# VGA.net
KiCad netlist of a schematic drawn in Altium Designer
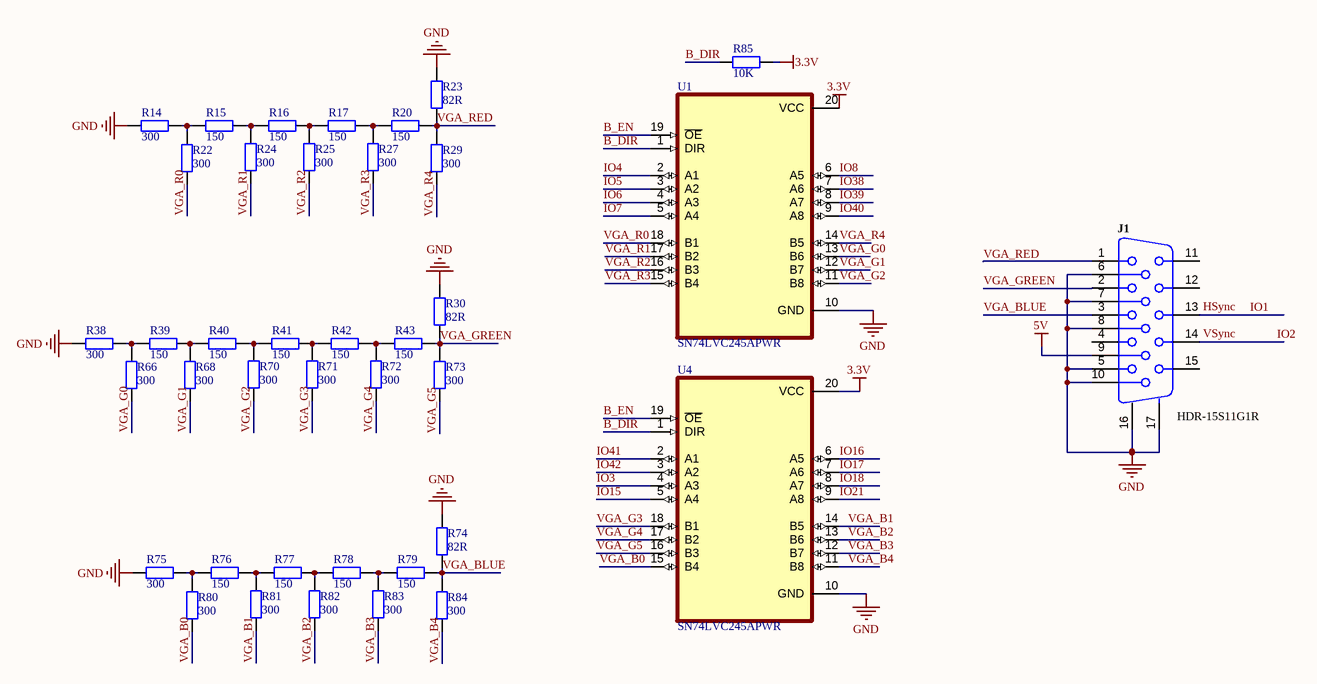
[diagram p0: VGA.SchDoc]

(export (version "E")
  (design (tool "Eeschema 10.0.6"))
  (components
    (comp (ref "J1")
      (value "HDR-15S11G1R")
      (footprint "DB15-VGA-Female")
      (description "Socket, High-Density DB15 (HD15) R/A Female Through-hole")
      (libsource (lib "My Library") (part "CON 15 Female"))
    )
    (comp (ref "R14")
      (value "300")
      (footprint "RES-0603")
      (description "Resistor")
      (fields (field (name "Comment") "Res2") (field (name "PUBLISHER") "Altium Limited"))
      (libsource (lib "") (part "Res2_1"))
    )
    (comp (ref "R15")
      (value "150")
      (footprint "RES-0603")
      (description "Resistor")
      (fields (field (name "Comment") "Res2") (field (name "PUBLISHER") "Altium Limited"))
      (libsource (lib "") (part "Res2_1"))
    )
    (comp (ref "R16")
      (value "150")
      (footprint "RES-0603")
      (description "Resistor")
      (fields (field (name "Comment") "Res2") (field (name "PUBLISHER") "Altium Limited"))
      (libsource (lib "") (part "Res2_1"))
    )
    (comp (ref "R17")
      (value "150")
      (footprint "RES-0603")
      (description "Resistor")
      (fields (field (name "Comment") "Res2") (field (name "PUBLISHER") "Altium Limited"))
      (libsource (lib "") (part "Res2_1"))
    )
    (comp (ref "R20")
      (value "150")
      (footprint "RES-0603")
      (description "Resistor")
      (fields (field (name "Comment") "Res2") (field (name "PUBLISHER") "Altium Limited"))
      (libsource (lib "") (part "Res2_1"))
    )
    (comp (ref "R22")
      (value "300")
      (footprint "RES-0603")
      (description "Resistor")
      (fields (field (name "Comment") "Res2") (field (name "PUBLISHER") "Altium Limited"))
      (libsource (lib "Miscellaneous Devices") (part "Res2"))
    )
    (comp (ref "R23")
      (value "82R")
      (footprint "RES-0603")
      (description "Resistor")
      (fields (field (name "Comment") "Res2") (field (name "PUBLISHER") "Altium Limited"))
      (libsource (lib "") (part "Res2_2"))
    )
    (comp (ref "R24")
      (value "300")
      (footprint "RES-0603")
      (description "Resistor")
      (fields (field (name "Comment") "Res2") (field (name "PUBLISHER") "Altium Limited"))
      (libsource (lib "Miscellaneous Devices") (part "Res2"))
    )
    (comp (ref "R25")
      (value "300")
      (footprint "RES-0603")
      (description "Resistor")
      (fields (field (name "Comment") "Res2") (field (name "PUBLISHER") "Altium Limited"))
      (libsource (lib "Miscellaneous Devices") (part "Res2"))
    )
    (comp (ref "R27")
      (value "300")
      (footprint "RES-0603")
      (description "Resistor")
      (fields (field (name "Comment") "Res2") (field (name "PUBLISHER") "Altium Limited"))
      (libsource (lib "Miscellaneous Devices") (part "Res2"))
    )
    (comp (ref "R29")
      (value "300")
      (footprint "RES-0603")
      (description "Resistor")
      (fields (field (name "Comment") "Res2") (field (name "PUBLISHER") "Altium Limited"))
      (libsource (lib "Miscellaneous Devices") (part "Res2"))
    )
    (comp (ref "R30")
      (value "82R")
      (footprint "RES-0603")
      (description "Resistor")
      (fields (field (name "Comment") "Res2") (field (name "PUBLISHER") "Altium Limited"))
      (libsource (lib "") (part "Res2_2"))
    )
    (comp (ref "R38")
      (value "300")
      (footprint "RES-0603")
      (description "Resistor")
      (fields (field (name "Comment") "Res2") (field (name "PUBLISHER") "Altium Limited"))
      (libsource (lib "") (part "Res2_1"))
    )
    (comp (ref "R39")
      (value "150")
      (footprint "RES-0603")
      (description "Resistor")
      (fields (field (name "Comment") "Res2") (field (name "PUBLISHER") "Altium Limited"))
      (libsource (lib "") (part "Res2_1"))
    )
    (comp (ref "R40")
      (value "150")
      (footprint "RES-0603")
      (description "Resistor")
      (fields (field (name "Comment") "Res2") (field (name "PUBLISHER") "Altium Limited"))
      (libsource (lib "") (part "Res2_1"))
    )
    (comp (ref "R41")
      (value "150")
      (footprint "RES-0603")
      (description "Resistor")
      (fields (field (name "Comment") "Res2") (field (name "PUBLISHER") "Altium Limited"))
      (libsource (lib "") (part "Res2_1"))
    )
    (comp (ref "R42")
      (value "150")
      (footprint "RES-0603")
      (description "Resistor")
      (fields (field (name "Comment") "Res2") (field (name "PUBLISHER") "Altium Limited"))
      (libsource (lib "") (part "Res2_1"))
    )
    (comp (ref "R43")
      (value "150")
      (footprint "RES-0603")
      (description "Resistor")
      (fields (field (name "Comment") "Res2") (field (name "PUBLISHER") "Altium Limited"))
      (libsource (lib "") (part "Res2_1"))
    )
    (comp (ref "R66")
      (value "300")
      (footprint "RES-0603")
      (description "Resistor")
      (fields (field (name "Comment") "Res2") (field (name "PUBLISHER") "Altium Limited"))
      (libsource (lib "Miscellaneous Devices") (part "Res2"))
    )
    (comp (ref "R68")
      (value "300")
      (footprint "RES-0603")
      (description "Resistor")
      (fields (field (name "Comment") "Res2") (field (name "PUBLISHER") "Altium Limited"))
      (libsource (lib "Miscellaneous Devices") (part "Res2"))
    )
    (comp (ref "R70")
      (value "300")
      (footprint "RES-0603")
      (description "Resistor")
      (fields (field (name "Comment") "Res2") (field (name "PUBLISHER") "Altium Limited"))
      (libsource (lib "Miscellaneous Devices") (part "Res2"))
    )
    (comp (ref "R71")
      (value "300")
      (footprint "RES-0603")
      (description "Resistor")
      (fields (field (name "Comment") "Res2") (field (name "PUBLISHER") "Altium Limited"))
      (libsource (lib "Miscellaneous Devices") (part "Res2"))
    )
    (comp (ref "R72")
      (value "300")
      (footprint "RES-0603")
      (description "Resistor")
      (fields (field (name "Comment") "Res2") (field (name "PUBLISHER") "Altium Limited"))
      (libsource (lib "Miscellaneous Devices") (part "Res2"))
    )
    (comp (ref "R73")
      (value "300")
      (footprint "RES-0603")
      (description "Resistor")
      (fields (field (name "Comment") "Res2") (field (name "PUBLISHER") "Altium Limited"))
      (libsource (lib "Miscellaneous Devices") (part "Res2"))
    )
    (comp (ref "R74")
      (value "82R")
      (footprint "RES-0603")
      (description "Resistor")
      (fields (field (name "Comment") "Res2") (field (name "PUBLISHER") "Altium Limited"))
      (libsource (lib "") (part "Res2_2"))
    )
    (comp (ref "R75")
      (value "300")
      (footprint "RES-0603")
      (description "Resistor")
      (fields (field (name "Comment") "Res2") (field (name "PUBLISHER") "Altium Limited"))
      (libsource (lib "") (part "Res2_1"))
    )
    (comp (ref "R76")
      (value "150")
      (footprint "RES-0603")
      (description "Resistor")
      (fields (field (name "Comment") "Res2") (field (name "PUBLISHER") "Altium Limited"))
      (libsource (lib "") (part "Res2_1"))
    )
    (comp (ref "R77")
      (value "150")
      (footprint "RES-0603")
      (description "Resistor")
      (fields (field (name "Comment") "Res2") (field (name "PUBLISHER") "Altium Limited"))
      (libsource (lib "") (part "Res2_1"))
    )
    (comp (ref "R78")
      (value "150")
      (footprint "RES-0603")
      (description "Resistor")
      (fields (field (name "Comment") "Res2") (field (name "PUBLISHER") "Altium Limited"))
      (libsource (lib "") (part "Res2_1"))
    )
    (comp (ref "R79")
      (value "150")
      (footprint "RES-0603")
      (description "Resistor")
      (fields (field (name "Comment") "Res2") (field (name "PUBLISHER") "Altium Limited"))
      (libsource (lib "") (part "Res2_1"))
    )
    (comp (ref "R80")
      (value "300")
      (footprint "RES-0603")
      (description "Resistor")
      (fields (field (name "Comment") "Res2") (field (name "PUBLISHER") "Altium Limited"))
      (libsource (lib "Miscellaneous Devices") (part "Res2"))
    )
    (comp (ref "R81")
      (value "300")
      (footprint "RES-0603")
      (description "Resistor")
      (fields (field (name "Comment") "Res2") (field (name "PUBLISHER") "Altium Limited"))
      (libsource (lib "Miscellaneous Devices") (part "Res2"))
    )
    (comp (ref "R82")
      (value "300")
      (footprint "RES-0603")
      (description "Resistor")
      (fields (field (name "Comment") "Res2") (field (name "PUBLISHER") "Altium Limited"))
      (libsource (lib "Miscellaneous Devices") (part "Res2"))
    )
    (comp (ref "R83")
      (value "300")
      (footprint "RES-0603")
      (description "Resistor")
      (fields (field (name "Comment") "Res2") (field (name "PUBLISHER") "Altium Limited"))
      (libsource (lib "Miscellaneous Devices") (part "Res2"))
    )
    (comp (ref "R84")
      (value "300")
      (footprint "RES-0603")
      (description "Resistor")
      (fields (field (name "Comment") "Res2") (field (name "PUBLISHER") "Altium Limited"))
      (libsource (lib "Miscellaneous Devices") (part "Res2"))
    )
    (comp (ref "R85")
      (value "10K")
      (footprint "RES-0603")
      (description "Resistor")
      (fields (field (name "Comment") "Res2") (field (name "PUBLISHER") "Altium Limited"))
      (libsource (lib "") (part "Res2_1"))
    )
    (comp (ref "U1")
      (value "SN74LVC245APWR")
      (footprint "SOP65P640X120-20N")
      (description "Octal Bus Transceiver With 3-State Outputs 20-TSSOP -40 to 125")
      (fields (field (name "MF") "Texas Instruments"))
      (libsource (lib "SN74LVC245APWR") (part "SN74LVC245APWR"))
    )
    (comp (ref "U4")
      (value "SN74LVC245APWR")
      (footprint "SOP65P640X120-20N")
      (description "Octal Bus Transceiver With 3-State Outputs 20-TSSOP -40 to 125")
      (fields (field (name "MF") "Texas Instruments"))
      (libsource (lib "SN74LVC245APWR") (part "SN74LVC245APWR"))
    )
  )
  (nets
    (net (code "1") (name "/B_DIR") (class "Default")
      (node (ref "R85") (pin "2") (pinfunction "2_2") (pintype "passive"))
      (node (ref "U1") (pin "1") (pinfunction "DIR_1") (pintype "input"))
      (node (ref "U4") (pin "1") (pinfunction "DIR_1") (pintype "input"))
    )
    (net (code "2") (name "/B_EN") (class "Default")
      (node (ref "U1") (pin "19") (pinfunction "~{OE}_19") (pintype "input"))
      (node (ref "U4") (pin "19") (pinfunction "~{OE}_19") (pintype "input"))
    )
    (net (code "4") (name "/IO1") (class "Default")
      (node (ref "J1") (pin "13") (pinfunction "13_13") (pintype "passive"))
    )
    (net (code "5") (name "/IO2") (class "Default")
      (node (ref "J1") (pin "14") (pinfunction "14_14") (pintype "passive"))
    )
    (net (code "6") (name "/IO3") (class "Default")
      (node (ref "U4") (pin "4") (pinfunction "A3_4") (pintype "bidirectional"))
    )
    (net (code "7") (name "/IO4") (class "Default")
      (node (ref "U1") (pin "2") (pinfunction "A1_2") (pintype "bidirectional"))
    )
    (net (code "8") (name "/IO5") (class "Default")
      (node (ref "U1") (pin "3") (pinfunction "A2_3") (pintype "bidirectional"))
    )
    (net (code "9") (name "/IO6") (class "Default")
      (node (ref "U1") (pin "4") (pinfunction "A3_4") (pintype "bidirectional"))
    )
    (net (code "10") (name "/IO7") (class "Default")
      (node (ref "U1") (pin "5") (pinfunction "A4_5") (pintype "bidirectional"))
    )
    (net (code "11") (name "/IO8") (class "Default")
      (node (ref "U1") (pin "6") (pinfunction "A5_6") (pintype "bidirectional"))
    )
    (net (code "12") (name "/IO15") (class "Default")
      (node (ref "U4") (pin "5") (pinfunction "A4_5") (pintype "bidirectional"))
    )
    (net (code "13") (name "/IO16") (class "Default")
      (node (ref "U4") (pin "6") (pinfunction "A5_6") (pintype "bidirectional"))
    )
    (net (code "14") (name "/IO17") (class "Default")
      (node (ref "U4") (pin "7") (pinfunction "A6_7") (pintype "bidirectional"))
    )
    (net (code "15") (name "/IO18") (class "Default")
      (node (ref "U4") (pin "8") (pinfunction "A7_8") (pintype "bidirectional"))
    )
    (net (code "16") (name "/IO21") (class "Default")
      (node (ref "U4") (pin "9") (pinfunction "A8_9") (pintype "bidirectional"))
    )
    (net (code "17") (name "/IO38") (class "Default")
      (node (ref "U1") (pin "7") (pinfunction "A6_7") (pintype "bidirectional"))
    )
    (net (code "18") (name "/IO39") (class "Default")
      (node (ref "U1") (pin "8") (pinfunction "A7_8") (pintype "bidirectional"))
    )
    (net (code "19") (name "/IO40") (class "Default")
      (node (ref "U1") (pin "9") (pinfunction "A8_9") (pintype "bidirectional"))
    )
    (net (code "20") (name "/IO41") (class "Default")
      (node (ref "U4") (pin "2") (pinfunction "A1_2") (pintype "bidirectional"))
    )
    (net (code "21") (name "/IO42") (class "Default")
      (node (ref "U4") (pin "3") (pinfunction "A2_3") (pintype "bidirectional"))
    )
    (net (code "22") (name "/VGA_B0") (class "Default")
      (node (ref "R80") (pin "2") (pinfunction "2_2") (pintype "passive"))
      (node (ref "U4") (pin "15") (pinfunction "B4_15") (pintype "bidirectional"))
    )
    (net (code "23") (name "/VGA_B1") (class "Default")
      (node (ref "R81") (pin "2") (pinfunction "2_2") (pintype "passive"))
      (node (ref "U4") (pin "14") (pinfunction "B5_14") (pintype "bidirectional"))
    )
    (net (code "24") (name "/VGA_B2") (class "Default")
      (node (ref "R82") (pin "2") (pinfunction "2_2") (pintype "passive"))
      (node (ref "U4") (pin "13") (pinfunction "B6_13") (pintype "bidirectional"))
    )
    (net (code "25") (name "/VGA_B3") (class "Default")
      (node (ref "R83") (pin "2") (pinfunction "2_2") (pintype "passive"))
      (node (ref "U4") (pin "12") (pinfunction "B7_12") (pintype "bidirectional"))
    )
    (net (code "26") (name "/VGA_B4") (class "Default")
      (node (ref "R84") (pin "2") (pinfunction "2_2") (pintype "passive"))
      (node (ref "U4") (pin "11") (pinfunction "B8_11") (pintype "bidirectional"))
    )
    (net (code "27") (name "/VGA_BLUE") (class "Default")
      (node (ref "J1") (pin "3") (pinfunction "3_3") (pintype "passive"))
      (node (ref "R74") (pin "1") (pinfunction "1_1") (pintype "passive"))
      (node (ref "R79") (pin "1") (pinfunction "1_1") (pintype "passive"))
      (node (ref "R84") (pin "1") (pinfunction "1_1") (pintype "passive"))
    )
    (net (code "28") (name "/VGA_G0") (class "Default")
      (node (ref "R66") (pin "2") (pinfunction "2_2") (pintype "passive"))
      (node (ref "U1") (pin "13") (pinfunction "B6_13") (pintype "bidirectional"))
    )
    (net (code "29") (name "/VGA_G1") (class "Default")
      (node (ref "R68") (pin "2") (pinfunction "2_2") (pintype "passive"))
      (node (ref "U1") (pin "12") (pinfunction "B7_12") (pintype "bidirectional"))
    )
    (net (code "30") (name "/VGA_G2") (class "Default")
      (node (ref "R70") (pin "2") (pinfunction "2_2") (pintype "passive"))
      (node (ref "U1") (pin "11") (pinfunction "B8_11") (pintype "bidirectional"))
    )
    (net (code "31") (name "/VGA_G3") (class "Default")
      (node (ref "R71") (pin "2") (pinfunction "2_2") (pintype "passive"))
      (node (ref "U4") (pin "18") (pinfunction "B1_18") (pintype "bidirectional"))
    )
    (net (code "32") (name "/VGA_G4") (class "Default")
      (node (ref "R72") (pin "2") (pinfunction "2_2") (pintype "passive"))
      (node (ref "U4") (pin "17") (pinfunction "B2_17") (pintype "bidirectional"))
    )
    (net (code "33") (name "/VGA_G5") (class "Default")
      (node (ref "R73") (pin "2") (pinfunction "2_2") (pintype "passive"))
      (node (ref "U4") (pin "16") (pinfunction "B3_16") (pintype "bidirectional"))
    )
    (net (code "34") (name "/VGA_GREEN") (class "Default")
      (node (ref "J1") (pin "2") (pinfunction "2_2") (pintype "passive"))
      (node (ref "R30") (pin "1") (pinfunction "1_1") (pintype "passive"))
      (node (ref "R43") (pin "1") (pinfunction "1_1") (pintype "passive"))
      (node (ref "R73") (pin "1") (pinfunction "1_1") (pintype "passive"))
    )
    (net (code "35") (name "/VGA_R0") (class "Default")
      (node (ref "R22") (pin "2") (pinfunction "2_2") (pintype "passive"))
      (node (ref "U1") (pin "18") (pinfunction "B1_18") (pintype "bidirectional"))
    )
    (net (code "36") (name "/VGA_R1") (class "Default")
      (node (ref "R24") (pin "2") (pinfunction "2_2") (pintype "passive"))
      (node (ref "U1") (pin "17") (pinfunction "B2_17") (pintype "bidirectional"))
    )
    (net (code "37") (name "/VGA_R2") (class "Default")
      (node (ref "R25") (pin "2") (pinfunction "2_2") (pintype "passive"))
      (node (ref "U1") (pin "16") (pinfunction "B3_16") (pintype "bidirectional"))
    )
    (net (code "38") (name "/VGA_R3") (class "Default")
      (node (ref "R27") (pin "2") (pinfunction "2_2") (pintype "passive"))
      (node (ref "U1") (pin "15") (pinfunction "B4_15") (pintype "bidirectional"))
    )
    (net (code "39") (name "/VGA_R4") (class "Default")
      (node (ref "R29") (pin "2") (pinfunction "2_2") (pintype "passive"))
      (node (ref "U1") (pin "14") (pinfunction "B5_14") (pintype "bidirectional"))
    )
    (net (code "40") (name "/VGA_RED") (class "Default")
      (node (ref "J1") (pin "1") (pinfunction "1_1") (pintype "passive"))
      (node (ref "R20") (pin "1") (pinfunction "1_1") (pintype "passive"))
      (node (ref "R23") (pin "1") (pinfunction "1_1") (pintype "passive"))
      (node (ref "R29") (pin "1") (pinfunction "1_1") (pintype "passive"))
    )
    (net (code "42") (name "3.3V") (class "Default")
      (node (ref "R85") (pin "1") (pinfunction "1_1") (pintype "passive"))
      (node (ref "U1") (pin "20") (pinfunction "VCC_20") (pintype "power_in"))
      (node (ref "U4") (pin "20") (pinfunction "VCC_20") (pintype "power_in"))
    )
    (net (code "43") (name "5V") (class "Default")
      (node (ref "J1") (pin "9") (pinfunction "9_9") (pintype "passive"))
    )
    (net (code "44") (name "GND") (class "Default")
      (node (ref "J1") (pin "10") (pinfunction "10_10") (pintype "power_in"))
      (node (ref "J1") (pin "16") (pinfunction "MH1_16") (pintype "passive"))
      (node (ref "J1") (pin "17") (pinfunction "MH2_17") (pintype "passive"))
      (node (ref "J1") (pin "5") (pinfunction "5_5") (pintype "power_in"))
      (node (ref "J1") (pin "6") (pinfunction "6_6") (pintype "power_in"))
      (node (ref "J1") (pin "7") (pinfunction "7_7") (pintype "power_in"))
      (node (ref "J1") (pin "8") (pinfunction "8_8") (pintype "power_in"))
      (node (ref "R14") (pin "2") (pinfunction "2_2") (pintype "passive"))
      (node (ref "R23") (pin "2") (pinfunction "2_2") (pintype "passive"))
      (node (ref "R30") (pin "2") (pinfunction "2_2") (pintype "passive"))
      (node (ref "R38") (pin "2") (pinfunction "2_2") (pintype "passive"))
      (node (ref "R74") (pin "2") (pinfunction "2_2") (pintype "passive"))
      (node (ref "R75") (pin "2") (pinfunction "2_2") (pintype "passive"))
      (node (ref "U1") (pin "10") (pinfunction "GND_10") (pintype "power_in"))
      (node (ref "U4") (pin "10") (pinfunction "GND_10") (pintype "power_in"))
    )
    (net (code "45") (name "Net-(R14-Pad1)") (class "Default")
      (node (ref "R14") (pin "1") (pinfunction "1_1") (pintype "passive"))
      (node (ref "R15") (pin "2") (pinfunction "2_2") (pintype "passive"))
      (node (ref "R22") (pin "1") (pinfunction "1_1") (pintype "passive"))
    )
    (net (code "46") (name "Net-(R15-Pad1)") (class "Default")
      (node (ref "R15") (pin "1") (pinfunction "1_1") (pintype "passive"))
      (node (ref "R16") (pin "2") (pinfunction "2_2") (pintype "passive"))
      (node (ref "R24") (pin "1") (pinfunction "1_1") (pintype "passive"))
    )
    (net (code "47") (name "Net-(R16-Pad1)") (class "Default")
      (node (ref "R16") (pin "1") (pinfunction "1_1") (pintype "passive"))
      (node (ref "R17") (pin "2") (pinfunction "2_2") (pintype "passive"))
      (node (ref "R25") (pin "1") (pinfunction "1_1") (pintype "passive"))
    )
    (net (code "48") (name "Net-(R17-Pad1)") (class "Default")
      (node (ref "R17") (pin "1") (pinfunction "1_1") (pintype "passive"))
      (node (ref "R20") (pin "2") (pinfunction "2_2") (pintype "passive"))
      (node (ref "R27") (pin "1") (pinfunction "1_1") (pintype "passive"))
    )
    (net (code "49") (name "Net-(R38-Pad1)") (class "Default")
      (node (ref "R38") (pin "1") (pinfunction "1_1") (pintype "passive"))
      (node (ref "R39") (pin "2") (pinfunction "2_2") (pintype "passive"))
      (node (ref "R66") (pin "1") (pinfunction "1_1") (pintype "passive"))
    )
    (net (code "50") (name "Net-(R39-Pad1)") (class "Default")
      (node (ref "R39") (pin "1") (pinfunction "1_1") (pintype "passive"))
      (node (ref "R40") (pin "2") (pinfunction "2_2") (pintype "passive"))
      (node (ref "R68") (pin "1") (pinfunction "1_1") (pintype "passive"))
    )
    (net (code "51") (name "Net-(R40-Pad1)") (class "Default")
      (node (ref "R40") (pin "1") (pinfunction "1_1") (pintype "passive"))
      (node (ref "R41") (pin "2") (pinfunction "2_2") (pintype "passive"))
      (node (ref "R70") (pin "1") (pinfunction "1_1") (pintype "passive"))
    )
    (net (code "52") (name "Net-(R41-Pad1)") (class "Default")
      (node (ref "R41") (pin "1") (pinfunction "1_1") (pintype "passive"))
      (node (ref "R42") (pin "2") (pinfunction "2_2") (pintype "passive"))
      (node (ref "R71") (pin "1") (pinfunction "1_1") (pintype "passive"))
    )
    (net (code "53") (name "Net-(R42-Pad1)") (class "Default")
      (node (ref "R42") (pin "1") (pinfunction "1_1") (pintype "passive"))
      (node (ref "R43") (pin "2") (pinfunction "2_2") (pintype "passive"))
      (node (ref "R72") (pin "1") (pinfunction "1_1") (pintype "passive"))
    )
    (net (code "54") (name "Net-(R75-Pad1)") (class "Default")
      (node (ref "R75") (pin "1") (pinfunction "1_1") (pintype "passive"))
      (node (ref "R76") (pin "2") (pinfunction "2_2") (pintype "passive"))
      (node (ref "R80") (pin "1") (pinfunction "1_1") (pintype "passive"))
    )
    (net (code "55") (name "Net-(R76-Pad1)") (class "Default")
      (node (ref "R76") (pin "1") (pinfunction "1_1") (pintype "passive"))
      (node (ref "R77") (pin "2") (pinfunction "2_2") (pintype "passive"))
      (node (ref "R81") (pin "1") (pinfunction "1_1") (pintype "passive"))
    )
    (net (code "56") (name "Net-(R77-Pad1)") (class "Default")
      (node (ref "R77") (pin "1") (pinfunction "1_1") (pintype "passive"))
      (node (ref "R78") (pin "2") (pinfunction "2_2") (pintype "passive"))
      (node (ref "R82") (pin "1") (pinfunction "1_1") (pintype "passive"))
    )
    (net (code "57") (name "Net-(R78-Pad1)") (class "Default")
      (node (ref "R78") (pin "1") (pinfunction "1_1") (pintype "passive"))
      (node (ref "R79") (pin "2") (pinfunction "2_2") (pintype "passive"))
      (node (ref "R83") (pin "1") (pinfunction "1_1") (pintype "passive"))
    )
    (net (code "58") (name "unconnected-(J1-Pad4)") (class "Default")
      (node (ref "J1") (pin "4") (pinfunction "4_4") (pintype "passive"))
    )
    (net (code "59") (name "unconnected-(J1-Pad11)") (class "Default")
      (node (ref "J1") (pin "11") (pinfunction "11_11") (pintype "power_in"))
    )
    (net (code "60") (name "unconnected-(J1-Pad12)") (class "Default")
      (node (ref "J1") (pin "12") (pinfunction "12_12") (pintype "passive"))
    )
    (net (code "61") (name "unconnected-(J1-Pad15)") (class "Default")
      (node (ref "J1") (pin "15") (pinfunction "15_15") (pintype "passive"))
    )
  )
)
